# USB.net
KiCad netlist of a schematic drawn in Altium Designer
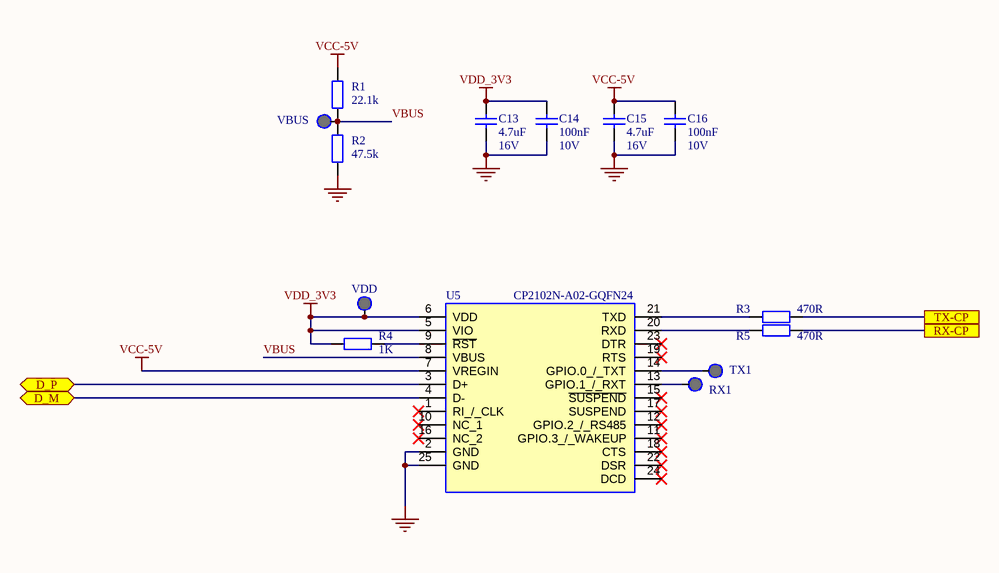
[diagram p0: USB.SchDoc]

(export (version "E")
  (design (tool "Eeschema 10.0.6"))
  (components
    (comp (ref "C13")
      (value "Capacitor")
      (footprint "CAPC1608N")
      (fields
        (field (name "PART NUMBER") "CAP-000000047")
        (field (name "VALUE 1") "4.7uF")
        (field (name "VALUE 2") "16V")
      )
      (libsource (lib "CMA") (part "Capacitor"))
    )
    (comp (ref "C14")
      (value "Capacitor")
      (footprint "CAPC1608N")
      (fields
        (field (name "PART NUMBER") "CAP-000000005")
        (field (name "VALUE 1") "100nF")
        (field (name "VALUE 2") "10V")
      )
      (libsource (lib "CMA") (part "Capacitor"))
    )
    (comp (ref "C15")
      (value "Capacitor")
      (footprint "CAPC1608N")
      (fields
        (field (name "PART NUMBER") "CAP-000000047")
        (field (name "VALUE 1") "4.7uF")
        (field (name "VALUE 2") "16V")
      )
      (libsource (lib "CMA") (part "Capacitor"))
    )
    (comp (ref "C16")
      (value "Capacitor")
      (footprint "CAPC1608N")
      (fields
        (field (name "PART NUMBER") "CAP-000000005")
        (field (name "VALUE 1") "100nF")
        (field (name "VALUE 2") "10V")
      )
      (libsource (lib "CMA") (part "Capacitor"))
    )
    (comp (ref "R1")
      (value "Resistor")
      (footprint "RESC1608N")
      (fields (field (name "PART NUMBER") "RES-000000017") (field (name "VALUE 1") "22.1k"))
      (libsource (lib "") (part "Resistor_1"))
    )
    (comp (ref "R2")
      (value "Resistor")
      (footprint "RESC1608N")
      (fields (field (name "PART NUMBER") "RES-000000018") (field (name "VALUE 1") "47.5k"))
      (libsource (lib "") (part "Resistor_1"))
    )
    (comp (ref "R3")
      (value "Resistor")
      (footprint "RESC1608N")
      (fields (field (name "PART NUMBER") "RES-000000016") (field (name "VALUE 1") "470R"))
      (libsource (lib "CMA") (part "Resistor"))
    )
    (comp (ref "R4")
      (value "Resistor")
      (footprint "RESC1608N")
      (fields (field (name "PART NUMBER") "RES-000000006") (field (name "VALUE 1") "1K"))
      (libsource (lib "") (part "Resistor_2"))
    )
    (comp (ref "R5")
      (value "Resistor")
      (footprint "RESC1608N")
      (fields (field (name "PART NUMBER") "RES-000000016") (field (name "VALUE 1") "470R"))
      (libsource (lib "CMA") (part "Resistor"))
    )
    (comp (ref "RX1")
      (value "Test Point")
      (footprint "TP")
      (fields (field (name "PART NUMBER") "MIS-000000003"))
      (libsource (lib "CMA") (part "TP"))
    )
    (comp (ref "TX1")
      (value "Test Point")
      (footprint "TP")
      (fields (field (name "PART NUMBER") "MIS-000000003"))
      (libsource (lib "CMA") (part "TP"))
    )
    (comp (ref "U5")
      (value "CP2102N-A02-GQFN24")
      (footprint "QFN-24")
      (fields (field (name "PART NUMBER") "MIS-000000025"))
      (libsource (lib "CMA") (part "CP2102N-A02-GQFN24"))
    )
    (comp (ref "VBUS")
      (value "Test Point")
      (footprint "TP")
      (fields (field (name "PART NUMBER") "MIS-000000003"))
      (libsource (lib "CMA") (part "TP"))
    )
    (comp (ref "VDD")
      (value "Test Point")
      (footprint "TP")
      (fields (field (name "PART NUMBER") "MIS-000000003"))
      (libsource (lib "CMA") (part "TP"))
    )
  )
  (nets
    (net (code "1") (name "/D_M") (class "Default")
      (node (ref "U5") (pin "4") (pinfunction "D-_4") (pintype "passive"))
    )
    (net (code "2") (name "/D_P") (class "Default")
      (node (ref "U5") (pin "3") (pinfunction "D+_3") (pintype "passive"))
    )
    (net (code "3") (name "/RX-CP") (class "Default")
      (node (ref "R5") (pin "1") (pinfunction "1_1") (pintype "passive"))
    )
    (net (code "4") (name "/TX-CP") (class "Default")
      (node (ref "R3") (pin "1") (pinfunction "1_1") (pintype "passive"))
    )
    (net (code "5") (name "/VBUS") (class "Default")
      (node (ref "R1") (pin "2") (pinfunction "2_2") (pintype "passive"))
      (node (ref "R2") (pin "1") (pinfunction "1_1") (pintype "passive"))
      (node (ref "U5") (pin "8") (pinfunction "VBUS_8") (pintype "passive"))
      (node (ref "VBUS") (pin "1") (pinfunction "1_1") (pintype "passive"))
    )
    (net (code "6") (name "GND") (class "Default")
      (node (ref "C13") (pin "1") (pinfunction "1_1") (pintype "passive"))
      (node (ref "C14") (pin "1") (pinfunction "1_1") (pintype "passive"))
      (node (ref "C15") (pin "1") (pinfunction "1_1") (pintype "passive"))
      (node (ref "C16") (pin "1") (pinfunction "1_1") (pintype "passive"))
      (node (ref "R2") (pin "2") (pinfunction "2_2") (pintype "passive"))
      (node (ref "U5") (pin "2") (pinfunction "GND_2") (pintype "passive"))
      (node (ref "U5") (pin "25") (pinfunction "GND_25") (pintype "passive"))
    )
    (net (code "7") (name "Net-(U5-GPIO.0_{slash}_TXT)") (class "Default")
      (node (ref "TX1") (pin "1") (pinfunction "1_1") (pintype "passive"))
      (node (ref "U5") (pin "14") (pinfunction "GPIO.0_/_TXT_14") (pintype "passive"))
    )
    (net (code "8") (name "Net-(U5-GPIO.1_{slash}_RXT)") (class "Default")
      (node (ref "RX1") (pin "1") (pinfunction "1_1") (pintype "passive"))
      (node (ref "U5") (pin "13") (pinfunction "GPIO.1_/_RXT_13") (pintype "passive"))
    )
    (net (code "9") (name "Net-(U5-RXD)") (class "Default")
      (node (ref "R5") (pin "2") (pinfunction "2_2") (pintype "passive"))
      (node (ref "U5") (pin "20") (pinfunction "RXD_20") (pintype "passive"))
    )
    (net (code "10") (name "Net-(U5-TXD)") (class "Default")
      (node (ref "R3") (pin "2") (pinfunction "2_2") (pintype "passive"))
      (node (ref "U5") (pin "21") (pinfunction "TXD_21") (pintype "passive"))
    )
    (net (code "11") (name "Net-(U5-~{RST})") (class "Default")
      (node (ref "R4") (pin "2") (pinfunction "2_2") (pintype "passive"))
      (node (ref "U5") (pin "9") (pinfunction "~{RST}_9") (pintype "passive"))
    )
    (net (code "12") (name "VCC-5V") (class "Default")
      (node (ref "C15") (pin "2") (pinfunction "2_2") (pintype "passive"))
      (node (ref "C16") (pin "2") (pinfunction "2_2") (pintype "passive"))
      (node (ref "R1") (pin "1") (pinfunction "1_1") (pintype "passive"))
      (node (ref "U5") (pin "7") (pinfunction "VREGIN_7") (pintype "passive"))
    )
    (net (code "13") (name "VDD_3V3") (class "Default")
      (node (ref "C13") (pin "2") (pinfunction "2_2") (pintype "passive"))
      (node (ref "C14") (pin "2") (pinfunction "2_2") (pintype "passive"))
      (node (ref "R4") (pin "1") (pinfunction "1_1") (pintype "passive"))
      (node (ref "U5") (pin "5") (pinfunction "VIO_5") (pintype "passive"))
      (node (ref "U5") (pin "6") (pinfunction "VDD_6") (pintype "passive"))
      (node (ref "VDD") (pin "1") (pinfunction "1_1") (pintype "passive"))
    )
    (net (code "14") (name "unconnected-(U5-CTS-Pad18)") (class "Default")
      (node (ref "U5") (pin "18") (pinfunction "CTS_18") (pintype "passive+no_connect"))
    )
    (net (code "15") (name "unconnected-(U5-DCD-Pad24)") (class "Default")
      (node (ref "U5") (pin "24") (pinfunction "DCD_24") (pintype "passive+no_connect"))
    )
    (net (code "16") (name "unconnected-(U5-DSR-Pad22)") (class "Default")
      (node (ref "U5") (pin "22") (pinfunction "DSR_22") (pintype "passive+no_connect"))
    )
    (net (code "17") (name "unconnected-(U5-DTR-Pad23)") (class "Default")
      (node (ref "U5") (pin "23") (pinfunction "DTR_23") (pintype "passive+no_connect"))
    )
    (net (code "18") (name "unconnected-(U5-GPIO.2_{slash}_RS485-Pad12)") (class "Default")
      (node (ref "U5") (pin "12") (pinfunction "GPIO.2_/_RS485_12") (pintype "passive+no_connect"))
    )
    (net (code "19") (name "unconnected-(U5-GPIO.3_{slash}_WAKEUP-Pad11)") (class "Default")
      (node (ref "U5") (pin "11") (pinfunction "GPIO.3_/_WAKEUP_11") (pintype "passive+no_connect"))
    )
    (net (code "20") (name "unconnected-(U5-NC_1-Pad10)") (class "Default")
      (node (ref "U5") (pin "10") (pinfunction "NC_1_10") (pintype "passive+no_connect"))
    )
    (net (code "21") (name "unconnected-(U5-NC_2-Pad16)") (class "Default")
      (node (ref "U5") (pin "16") (pinfunction "NC_2_16") (pintype "passive+no_connect"))
    )
    (net (code "22") (name "unconnected-(U5-RI_{slash}_CLK-Pad1)") (class "Default")
      (node (ref "U5") (pin "1") (pinfunction "RI_/_CLK_1") (pintype "passive+no_connect"))
    )
    (net (code "23") (name "unconnected-(U5-RTS-Pad19)") (class "Default")
      (node (ref "U5") (pin "19") (pinfunction "RTS_19") (pintype "passive+no_connect"))
    )
    (net (code "24") (name "unconnected-(U5-SUSPEND-Pad17)") (class "Default")
      (node (ref "U5") (pin "17") (pinfunction "SUSPEND_17") (pintype "passive+no_connect"))
    )
    (net (code "25") (name "unconnected-(U5-~{SUSPEND}-Pad15)") (class "Default")
      (node (ref "U5") (pin "15") (pinfunction "~{SUSPEND}_15") (pintype "passive+no_connect"))
    )
  )
)
